# bleep.net
KiCad netlist of a schematic drawn in EAGLE
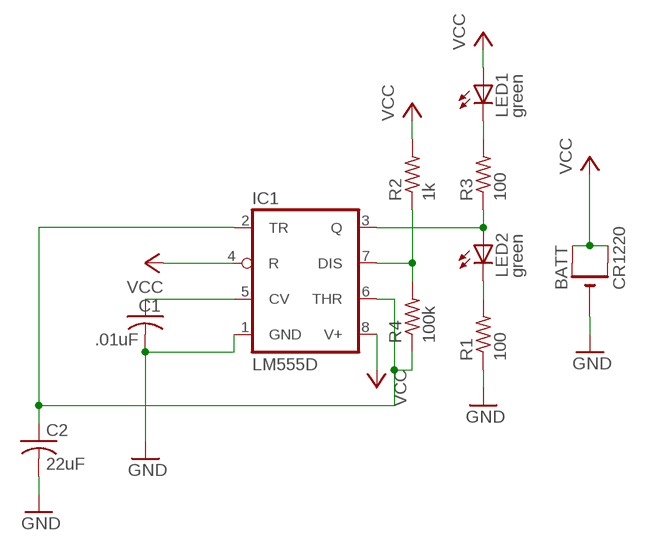
[diagram p0: schematic, sheet 1]

(export (version "E")
  (design (tool "Eeschema 10.0.6"))
  (components
    (comp (ref "BATT")
      (value "CR1220")
      (footprint "eagle-import:CR1220-SMD")
      (libsource (lib "eagle-import") (part "CR1220SMT"))
    )
    (comp (ref "C1")
      (value ".01uF")
      (footprint "eagle-import:C0805")
      (libsource (lib "eagle-import") (part "C-USC0805"))
    )
    (comp (ref "C2")
      (value "22uF")
      (footprint "eagle-import:C0805")
      (libsource (lib "eagle-import") (part "C-USC0805"))
    )
    (comp (ref "IC1")
      (value "LM555D")
      (footprint "eagle-import:SO08")
      (libsource (lib "eagle-import") (part "555DLM"))
    )
    (comp (ref "LED1")
      (value "green")
      (footprint "eagle-import:CHIPLED_0805")
      (libsource (lib "eagle-import") (part "LEDCHIPLED_0805"))
    )
    (comp (ref "LED2")
      (value "green")
      (footprint "eagle-import:CHIPLED_0805")
      (libsource (lib "eagle-import") (part "LEDCHIPLED_0805"))
    )
    (comp (ref "R1")
      (value "100")
      (footprint "eagle-import:R0805")
      (libsource (lib "eagle-import") (part "R-US_R0805"))
    )
    (comp (ref "R2")
      (value "1k")
      (footprint "eagle-import:R0805")
      (libsource (lib "eagle-import") (part "R-US_R0805"))
    )
    (comp (ref "R3")
      (value "100")
      (footprint "eagle-import:R0805")
      (libsource (lib "eagle-import") (part "R-US_R0805"))
    )
    (comp (ref "R4")
      (value "100k")
      (footprint "eagle-import:R0805")
      (libsource (lib "eagle-import") (part "R-US_R0805"))
    )
  )
  (nets
    (net (code "1") (name "GND") (class "Default")
      (node (ref "BATT") (pin "-") (pinfunction "-_-") (pintype "passive"))
      (node (ref "C1") (pin "2") (pinfunction "2_2") (pintype "passive"))
      (node (ref "C2") (pin "2") (pinfunction "2_2") (pintype "passive"))
      (node (ref "IC1") (pin "1") (pinfunction "GND_1") (pintype "power_in"))
      (node (ref "R1") (pin "1") (pinfunction "1_1") (pintype "passive"))
    )
    (net (code "2") (name "Net-(IC1-CV)") (class "Default")
      (node (ref "C1") (pin "1") (pinfunction "1_1") (pintype "passive"))
      (node (ref "IC1") (pin "5") (pinfunction "CV_5") (pintype "input"))
    )
    (net (code "3") (name "Net-(IC1-DIS)") (class "Default")
      (node (ref "IC1") (pin "7") (pinfunction "DIS_7") (pintype "input"))
      (node (ref "R2") (pin "1") (pinfunction "1_1") (pintype "passive"))
      (node (ref "R4") (pin "2") (pinfunction "2_2") (pintype "passive"))
    )
    (net (code "4") (name "Net-(IC1-Q)") (class "Default")
      (node (ref "IC1") (pin "3") (pinfunction "Q_3") (pintype "output"))
      (node (ref "LED2") (pin "A") (pinfunction "A_A") (pintype "passive"))
      (node (ref "R3") (pin "1") (pinfunction "1_1") (pintype "passive"))
    )
    (net (code "5") (name "Net-(IC1-THR)") (class "Default")
      (node (ref "C2") (pin "1") (pinfunction "1_1") (pintype "passive"))
      (node (ref "IC1") (pin "2") (pinfunction "TR_2") (pintype "input"))
      (node (ref "IC1") (pin "6") (pinfunction "THR_6") (pintype "input"))
      (node (ref "R4") (pin "1") (pinfunction "1_1") (pintype "passive"))
    )
    (net (code "6") (name "Net-(LED1-PadC)") (class "Default")
      (node (ref "LED1") (pin "C") (pinfunction "C_C") (pintype "passive"))
      (node (ref "R3") (pin "2") (pinfunction "2_2") (pintype "passive"))
    )
    (net (code "7") (name "Net-(LED2-PadC)") (class "Default")
      (node (ref "LED2") (pin "C") (pinfunction "C_C") (pintype "passive"))
      (node (ref "R1") (pin "2") (pinfunction "2_2") (pintype "passive"))
    )
    (net (code "8") (name "VCC") (class "Default")
      (node (ref "BATT") (pin "+$1") (pinfunction "+_+$1") (pintype "passive"))
      (node (ref "BATT") (pin "+$2") (pinfunction "+1_+$2") (pintype "passive"))
      (node (ref "IC1") (pin "4") (pinfunction "R_4") (pintype "input"))
      (node (ref "IC1") (pin "8") (pinfunction "V+_8") (pintype "power_in"))
      (node (ref "LED1") (pin "A") (pinfunction "A_A") (pintype "passive"))
      (node (ref "R2") (pin "2") (pinfunction "2_2") (pintype "passive"))
    )
  )
)
